# mLRS-tx-dual-base-v042-np.net
KiCad netlist of a schematic drawn in EAGLE
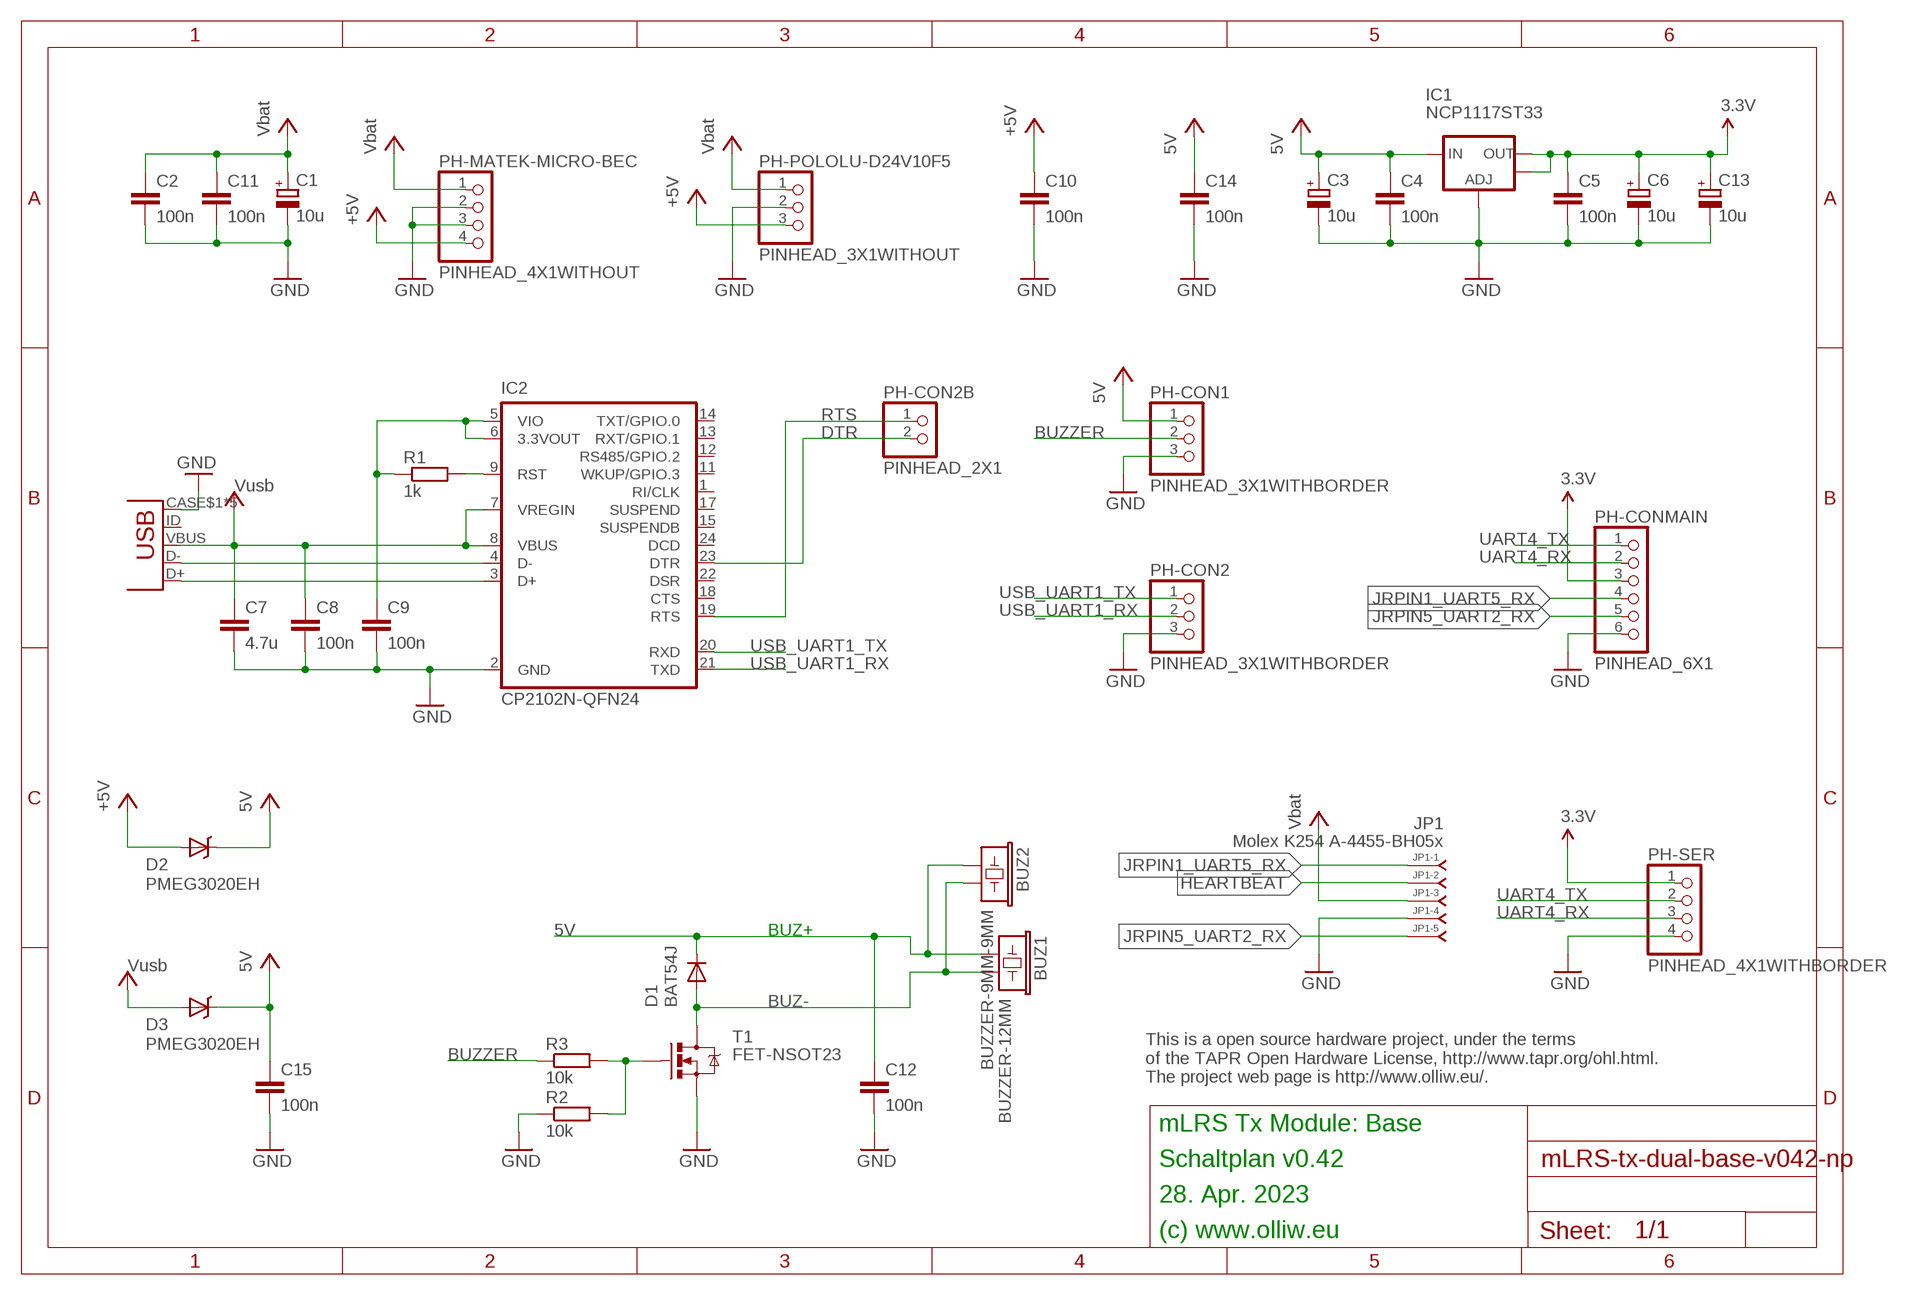
[diagram p0: schematic, sheet 1]

(export (version "E")
  (design (tool "Eeschema 10.0.6"))
  (components
    (comp (ref "BUZ1")
      (value "BUZZER-12MM")
      (footprint "eagle-import:BUZZER-12MM")
      (libsource (lib "eagle-import") (part "BUZZER-12MM"))
    )
    (comp (ref "BUZ2")
      (value "BUZZER-9MM-9MM")
      (footprint "eagle-import:BUZZER-9MM")
      (libsource (lib "eagle-import") (part "BUZZER-9MM-9MM"))
    )
    (comp (ref "C1")
      (value "10u")
      (footprint "eagle-import:SMC_A")
      (libsource (lib "eagle-import") (part "CPOL-EUSMCA"))
    )
    (comp (ref "C2")
      (value "100n")
      (footprint "eagle-import:C0603")
      (libsource (lib "eagle-import") (part "C-EUC0603"))
    )
    (comp (ref "C3")
      (value "10u")
      (footprint "eagle-import:SMC_A")
      (libsource (lib "eagle-import") (part "CPOL-EUSMCA"))
    )
    (comp (ref "C4")
      (value "100n")
      (footprint "eagle-import:C0603")
      (libsource (lib "eagle-import") (part "C-EUC0603"))
    )
    (comp (ref "C5")
      (value "100n")
      (footprint "eagle-import:C0603")
      (libsource (lib "eagle-import") (part "C-EUC0603"))
    )
    (comp (ref "C6")
      (value "10u")
      (footprint "eagle-import:SMC_A")
      (libsource (lib "eagle-import") (part "CPOL-EUSMCA"))
    )
    (comp (ref "C7")
      (value "4.7u")
      (footprint "eagle-import:C0603")
      (libsource (lib "eagle-import") (part "C-EUC0603"))
    )
    (comp (ref "C8")
      (value "100n")
      (footprint "eagle-import:C0402")
      (libsource (lib "eagle-import") (part "C-EUC0402"))
    )
    (comp (ref "C9")
      (value "100n")
      (footprint "eagle-import:C0402")
      (libsource (lib "eagle-import") (part "C-EUC0402"))
    )
    (comp (ref "C10")
      (value "100n")
      (footprint "eagle-import:C0603")
      (libsource (lib "eagle-import") (part "C-EUC0603"))
    )
    (comp (ref "C11")
      (value "100n")
      (footprint "eagle-import:C0603")
      (libsource (lib "eagle-import") (part "C-EUC0603"))
    )
    (comp (ref "C12")
      (value "100n")
      (footprint "eagle-import:C0603")
      (libsource (lib "eagle-import") (part "C-EUC0603"))
    )
    (comp (ref "C13")
      (value "10u")
      (footprint "eagle-import:SMC_A")
      (libsource (lib "eagle-import") (part "CPOL-EUSMCA"))
    )
    (comp (ref "C14")
      (value "100n")
      (footprint "eagle-import:C0603")
      (libsource (lib "eagle-import") (part "C-EUC0603"))
    )
    (comp (ref "C15")
      (value "100n")
      (footprint "eagle-import:C0603")
      (libsource (lib "eagle-import") (part "C-EUC0603"))
    )
    (comp (ref "D1")
      (value "BAT54J")
      (footprint "eagle-import:SOD110-R")
      (libsource (lib "eagle-import") (part "DIODE-SOD110-R"))
    )
    (comp (ref "D2")
      (value "PMEG3020EH")
      (footprint "eagle-import:SOD123W-DIODE")
      (libsource (lib "eagle-import") (part "DIODE-SCHOTTKYSOD123-W"))
    )
    (comp (ref "D3")
      (value "PMEG3020EH")
      (footprint "eagle-import:SOD123W-DIODE")
      (libsource (lib "eagle-import") (part "DIODE-SCHOTTKYSOD123-W"))
    )
    (comp (ref "IC1")
      (value "NCP1117ST33")
      (footprint "eagle-import:SOT223")
      (libsource (lib "eagle-import") (part "V_REG_LM1117SOT223"))
    )
    (comp (ref "IC2")
      (value "CP2102N-QFN24")
      (footprint "eagle-import:QFN24-CP2102N")
      (libsource (lib "eagle-import") (part "CP2102N-QFN24"))
    )
    (comp (ref "JP1")
      (value "Molex K254 A-4455-BH05x")
      (footprint "eagle-import:4455-B05")
      (libsource (lib "eagle-import") (part "4455-B05_S"))
    )
    (comp (ref "PH-CON1")
      (value "PINHEAD_3X1WITHBORDER")
      (footprint "eagle-import:PINHEAD_3X1")
      (libsource (lib "eagle-import") (part "PINHEAD_3X1WITHBORDER"))
    )
    (comp (ref "PH-CON2")
      (value "PINHEAD_3X1WITHBORDER")
      (footprint "eagle-import:PINHEAD_3X1")
      (libsource (lib "eagle-import") (part "PINHEAD_3X1WITHBORDER"))
    )
    (comp (ref "PH-CON2B")
      (value "PINHEAD_2X1")
      (footprint "eagle-import:PINHEAD_2X1")
      (libsource (lib "eagle-import") (part "PINHEAD_2X1"))
    )
    (comp (ref "PH-CONMAIN")
      (value "PINHEAD_6X1")
      (footprint "eagle-import:PINHEAD_6X1")
      (libsource (lib "eagle-import") (part "PINHEAD_6X1"))
    )
    (comp (ref "PH-MATEK-MICRO-BEC")
      (value "PINHEAD_4X1WITHOUT")
      (footprint "eagle-import:PINHEAD_4X1_WO")
      (libsource (lib "eagle-import") (part "PINHEAD_4X1WITHOUT"))
    )
    (comp (ref "PH-POLOLU-D24V10F5")
      (value "PINHEAD_3X1WITHOUT")
      (footprint "eagle-import:PINHEAD_3X1_WO")
      (libsource (lib "eagle-import") (part "PINHEAD_3X1WITHOUT"))
    )
    (comp (ref "PH-SER")
      (value "PINHEAD_4X1WITHBORDER")
      (footprint "eagle-import:PINHEAD_4X1")
      (libsource (lib "eagle-import") (part "PINHEAD_4X1WITHBORDER"))
    )
    (comp (ref "R1")
      (value "1k")
      (footprint "eagle-import:R0402")
      (libsource (lib "eagle-import") (part "R-EU_R0402"))
    )
    (comp (ref "R2")
      (value "10k")
      (footprint "eagle-import:R0402")
      (libsource (lib "eagle-import") (part "R-EU_R0402"))
    )
    (comp (ref "R3")
      (value "10k")
      (footprint "eagle-import:R0402")
      (libsource (lib "eagle-import") (part "R-EU_R0402"))
    )
    (comp (ref "T1")
      (value "FET-NSOT23")
      (footprint "eagle-import:SOT23")
      (libsource (lib "eagle-import") (part "FET-NSOT23"))
    )
    (comp (ref "USB1")
      (value "USB-MICROB-UP-NONPLATED")
      (footprint "eagle-import:USB-MICROB-UP-NONPLATED")
      (libsource (lib "eagle-import") (part "USB-MICROB-UP-NONPLATED"))
    )
  )
  (nets
    (net (code "1") (name "+5V") (class "Default")
      (node (ref "C10") (pin "1") (pinfunction "1_1") (pintype "passive"))
      (node (ref "D2") (pin "A") (pinfunction "A_A") (pintype "passive"))
      (node (ref "PH-MATEK-MICRO-BEC") (pin "4") (pinfunction "4_4") (pintype "passive"))
      (node (ref "PH-POLOLU-D24V10F5") (pin "3") (pinfunction "5_3") (pintype "passive"))
    )
    (net (code "2") (name "/BUZ-") (class "Default")
      (node (ref "BUZ1") (pin "-") (pinfunction "2_-") (pintype "passive"))
      (node (ref "BUZ2") (pin "-") (pinfunction "2_-") (pintype "passive"))
      (node (ref "D1") (pin "A") (pinfunction "A_A") (pintype "passive"))
      (node (ref "T1") (pin "3") (pinfunction "D_3") (pintype "passive"))
    )
    (net (code "3") (name "/BUZZER") (class "Default")
      (node (ref "PH-CON1") (pin "2") (pinfunction "3_2") (pintype "passive"))
      (node (ref "R3") (pin "1") (pinfunction "1_1") (pintype "passive"))
    )
    (net (code "4") (name "/DTR") (class "Default")
      (node (ref "IC2") (pin "23") (pinfunction "DTR_23") (pintype "output"))
      (node (ref "PH-CON2B") (pin "2") (pinfunction "2_2") (pintype "passive"))
    )
    (net (code "5") (name "/RTS") (class "Default")
      (node (ref "IC2") (pin "19") (pinfunction "RTS_19") (pintype "output"))
      (node (ref "PH-CON2B") (pin "1") (pinfunction "1_1") (pintype "passive"))
    )
    (net (code "6") (name "/UART4_RX") (class "Default")
      (node (ref "PH-CONMAIN") (pin "2") (pinfunction "2_2") (pintype "passive"))
      (node (ref "PH-SER") (pin "3") (pinfunction "3_3") (pintype "passive"))
    )
    (net (code "7") (name "/UART4_TX") (class "Default")
      (node (ref "PH-CONMAIN") (pin "1") (pinfunction "1_1") (pintype "passive"))
      (node (ref "PH-SER") (pin "2") (pinfunction "2_2") (pintype "passive"))
    )
    (net (code "8") (name "/USB_UART1_RX") (class "Default")
      (node (ref "IC2") (pin "21") (pinfunction "TXD_21") (pintype "output"))
      (node (ref "PH-CON2") (pin "2") (pinfunction "3_2") (pintype "passive"))
    )
    (net (code "9") (name "/USB_UART1_TX") (class "Default")
      (node (ref "IC2") (pin "20") (pinfunction "RXD_20") (pintype "input"))
      (node (ref "PH-CON2") (pin "1") (pinfunction "1_1") (pintype "passive"))
    )
    (net (code "10") (name "3.3V") (class "Default")
      (node (ref "C13") (pin "+") (pinfunction "+_+") (pintype "passive"))
      (node (ref "C5") (pin "1") (pinfunction "1_1") (pintype "passive"))
      (node (ref "C6") (pin "+") (pinfunction "+_+") (pintype "passive"))
      (node (ref "IC1") (pin "2") (pinfunction "OUT_2") (pintype "output"))
      (node (ref "IC1") (pin "4") (pinfunction "OUT_4") (pintype "output"))
      (node (ref "PH-CONMAIN") (pin "3") (pinfunction "3_3") (pintype "passive"))
      (node (ref "PH-SER") (pin "1") (pinfunction "1_1") (pintype "passive"))
    )
    (net (code "11") (name "5V") (class "Default")
      (node (ref "BUZ1") (pin "+") (pinfunction "1_+") (pintype "passive"))
      (node (ref "BUZ2") (pin "+") (pinfunction "1_+") (pintype "passive"))
      (node (ref "C12") (pin "1") (pinfunction "1_1") (pintype "passive"))
      (node (ref "C14") (pin "1") (pinfunction "1_1") (pintype "passive"))
      (node (ref "C15") (pin "1") (pinfunction "1_1") (pintype "passive"))
      (node (ref "C3") (pin "+") (pinfunction "+_+") (pintype "passive"))
      (node (ref "C4") (pin "1") (pinfunction "1_1") (pintype "passive"))
      (node (ref "D1") (pin "C") (pinfunction "C_C") (pintype "passive"))
      (node (ref "D2") (pin "C") (pinfunction "C_C") (pintype "passive"))
      (node (ref "D3") (pin "C") (pinfunction "C_C") (pintype "passive"))
      (node (ref "IC1") (pin "3") (pinfunction "IN_3") (pintype "input"))
      (node (ref "PH-CON1") (pin "1") (pinfunction "1_1") (pintype "passive"))
    )
    (net (code "12") (name "GND") (class "Default")
      (node (ref "C1") (pin "-") (pinfunction "-_-") (pintype "passive"))
      (node (ref "C10") (pin "2") (pinfunction "2_2") (pintype "passive"))
      (node (ref "C11") (pin "2") (pinfunction "2_2") (pintype "passive"))
      (node (ref "C12") (pin "2") (pinfunction "2_2") (pintype "passive"))
      (node (ref "C13") (pin "-") (pinfunction "-_-") (pintype "passive"))
      (node (ref "C14") (pin "2") (pinfunction "2_2") (pintype "passive"))
      (node (ref "C15") (pin "2") (pinfunction "2_2") (pintype "passive"))
      (node (ref "C2") (pin "2") (pinfunction "2_2") (pintype "passive"))
      (node (ref "C3") (pin "-") (pinfunction "-_-") (pintype "passive"))
      (node (ref "C4") (pin "2") (pinfunction "2_2") (pintype "passive"))
      (node (ref "C5") (pin "2") (pinfunction "2_2") (pintype "passive"))
      (node (ref "C6") (pin "-") (pinfunction "-_-") (pintype "passive"))
      (node (ref "C7") (pin "2") (pinfunction "2_2") (pintype "passive"))
      (node (ref "C8") (pin "2") (pinfunction "2_2") (pintype "passive"))
      (node (ref "C9") (pin "2") (pinfunction "2_2") (pintype "passive"))
      (node (ref "IC1") (pin "1") (pinfunction "ADJ_1") (pintype "input"))
      (node (ref "IC2") (pin "2") (pinfunction "GND_2") (pintype "power_in"))
      (node (ref "JP1") (pin "4") (pinfunction "J_4") (pintype "passive"))
      (node (ref "PH-CON1") (pin "3") (pinfunction "5_3") (pintype "passive"))
      (node (ref "PH-CON2") (pin "3") (pinfunction "5_3") (pintype "passive"))
      (node (ref "PH-CONMAIN") (pin "6") (pinfunction "6_6") (pintype "passive"))
      (node (ref "PH-MATEK-MICRO-BEC") (pin "2") (pinfunction "2_2") (pintype "passive"))
      (node (ref "PH-MATEK-MICRO-BEC") (pin "3") (pinfunction "3_3") (pintype "passive"))
      (node (ref "PH-POLOLU-D24V10F5") (pin "2") (pinfunction "3_2") (pintype "passive"))
      (node (ref "PH-SER") (pin "4") (pinfunction "4_4") (pintype "passive"))
      (node (ref "R2") (pin "1") (pinfunction "1_1") (pintype "passive"))
      (node (ref "T1") (pin "2") (pinfunction "S_2") (pintype "passive"))
      (node (ref "USB1") (pin "CASE$1") (pinfunction "GND_CASE$1") (pintype "bidirectional"))
      (node (ref "USB1") (pin "CASE$2") (pinfunction "GND_CASE$2") (pintype "bidirectional"))
      (node (ref "USB1") (pin "CASE$3") (pinfunction "GND_CASE$3") (pintype "bidirectional"))
      (node (ref "USB1") (pin "CASE$4") (pinfunction "GND_CASE$4") (pintype "bidirectional"))
      (node (ref "USB1") (pin "GND") (pinfunction "GND_GND") (pintype "bidirectional"))
    )
    (net (code "13") (name "HEARTBEAT") (class "Default")
      (node (ref "JP1") (pin "2") (pinfunction "J_2") (pintype "passive"))
    )
    (net (code "14") (name "JRPIN1_UART5_RX") (class "Default")
      (node (ref "JP1") (pin "1") (pinfunction "J_1") (pintype "passive"))
      (node (ref "PH-CONMAIN") (pin "4") (pinfunction "4_4") (pintype "passive"))
    )
    (net (code "15") (name "JRPIN5_UART2_RX") (class "Default")
      (node (ref "JP1") (pin "5") (pinfunction "J_5") (pintype "passive"))
      (node (ref "PH-CONMAIN") (pin "5") (pinfunction "5_5") (pintype "passive"))
    )
    (net (code "16") (name "Net-(IC2-3.3VOUT)") (class "Default")
      (node (ref "C9") (pin "1") (pinfunction "1_1") (pintype "passive"))
      (node (ref "IC2") (pin "5") (pinfunction "VIO_5") (pintype "power_in"))
      (node (ref "IC2") (pin "6") (pinfunction "3.3VOUT_6") (pintype "power_in"))
      (node (ref "R1") (pin "1") (pinfunction "1_1") (pintype "passive"))
    )
    (net (code "17") (name "Net-(IC2-D+)") (class "Default")
      (node (ref "IC2") (pin "3") (pinfunction "D+_3") (pintype "bidirectional"))
      (node (ref "USB1") (pin "D+") (pinfunction "D+_D+") (pintype "bidirectional"))
    )
    (net (code "18") (name "Net-(IC2-D-)") (class "Default")
      (node (ref "IC2") (pin "4") (pinfunction "D-_4") (pintype "bidirectional"))
      (node (ref "USB1") (pin "D-") (pinfunction "D-_D-") (pintype "bidirectional"))
    )
    (net (code "19") (name "Net-(IC2-RST)") (class "Default")
      (node (ref "IC2") (pin "9") (pinfunction "RST_9") (pintype "input"))
      (node (ref "R1") (pin "2") (pinfunction "2_2") (pintype "passive"))
    )
    (net (code "20") (name "Net-(T1-G)") (class "Default")
      (node (ref "R2") (pin "2") (pinfunction "2_2") (pintype "passive"))
      (node (ref "R3") (pin "2") (pinfunction "2_2") (pintype "passive"))
      (node (ref "T1") (pin "1") (pinfunction "G_1") (pintype "passive"))
    )
    (net (code "21") (name "Vbat") (class "Default")
      (node (ref "C1") (pin "+") (pinfunction "+_+") (pintype "passive"))
      (node (ref "C11") (pin "1") (pinfunction "1_1") (pintype "passive"))
      (node (ref "C2") (pin "1") (pinfunction "1_1") (pintype "passive"))
      (node (ref "JP1") (pin "3") (pinfunction "J_3") (pintype "passive"))
      (node (ref "PH-MATEK-MICRO-BEC") (pin "1") (pinfunction "1_1") (pintype "passive"))
      (node (ref "PH-POLOLU-D24V10F5") (pin "1") (pinfunction "1_1") (pintype "passive"))
    )
    (net (code "22") (name "Vusb") (class "Default")
      (node (ref "C7") (pin "1") (pinfunction "1_1") (pintype "passive"))
      (node (ref "C8") (pin "1") (pinfunction "1_1") (pintype "passive"))
      (node (ref "D3") (pin "A") (pinfunction "A_A") (pintype "passive"))
      (node (ref "IC2") (pin "7") (pinfunction "VREGIN_7") (pintype "power_in"))
      (node (ref "IC2") (pin "8") (pinfunction "VBUS_8") (pintype "input"))
      (node (ref "USB1") (pin "VBUS") (pinfunction "VBUS_VBUS") (pintype "bidirectional"))
    )
    (net (code "23") (name "unconnected-(IC2-CTS-Pad18)") (class "Default")
      (node (ref "IC2") (pin "18") (pinfunction "CTS_18") (pintype "input"))
    )
    (net (code "24") (name "unconnected-(IC2-DCD-Pad24)") (class "Default")
      (node (ref "IC2") (pin "24") (pinfunction "DCD_24") (pintype "input"))
    )
    (net (code "25") (name "unconnected-(IC2-DSR-Pad22)") (class "Default")
      (node (ref "IC2") (pin "22") (pinfunction "DSR_22") (pintype "input"))
    )
    (net (code "26") (name "unconnected-(IC2-RI{slash}CLK-Pad1)") (class "Default")
      (node (ref "IC2") (pin "1") (pinfunction "RI/CLK_1") (pintype "input"))
    )
    (net (code "27") (name "unconnected-(IC2-RS485{slash}GPIO.2-Pad12)") (class "Default")
      (node (ref "IC2") (pin "12") (pinfunction "RS485/GPIO.2_12") (pintype "bidirectional"))
    )
    (net (code "28") (name "unconnected-(IC2-RXT{slash}GPIO.1-Pad13)") (class "Default")
      (node (ref "IC2") (pin "13") (pinfunction "RXT/GPIO.1_13") (pintype "bidirectional"))
    )
    (net (code "29") (name "unconnected-(IC2-SUSPEND-Pad17)") (class "Default")
      (node (ref "IC2") (pin "17") (pinfunction "SUSPEND_17") (pintype "output"))
    )
    (net (code "30") (name "unconnected-(IC2-SUSPENDB-Pad15)") (class "Default")
      (node (ref "IC2") (pin "15") (pinfunction "SUSPENDB_15") (pintype "output"))
    )
    (net (code "31") (name "unconnected-(IC2-TXT{slash}GPIO.0-Pad14)") (class "Default")
      (node (ref "IC2") (pin "14") (pinfunction "TXT/GPIO.0_14") (pintype "bidirectional"))
    )
    (net (code "32") (name "unconnected-(IC2-WKUP{slash}GPIO.3-Pad11)") (class "Default")
      (node (ref "IC2") (pin "11") (pinfunction "WKUP/GPIO.3_11") (pintype "bidirectional"))
    )
    (net (code "33") (name "unconnected-(USB1-PadID)") (class "Default")
      (node (ref "USB1") (pin "ID") (pinfunction "ID_ID") (pintype "bidirectional"))
    )
  )
)
